# FEU31_Part3.net
KiCad netlist of a schematic drawn in Altium Designer
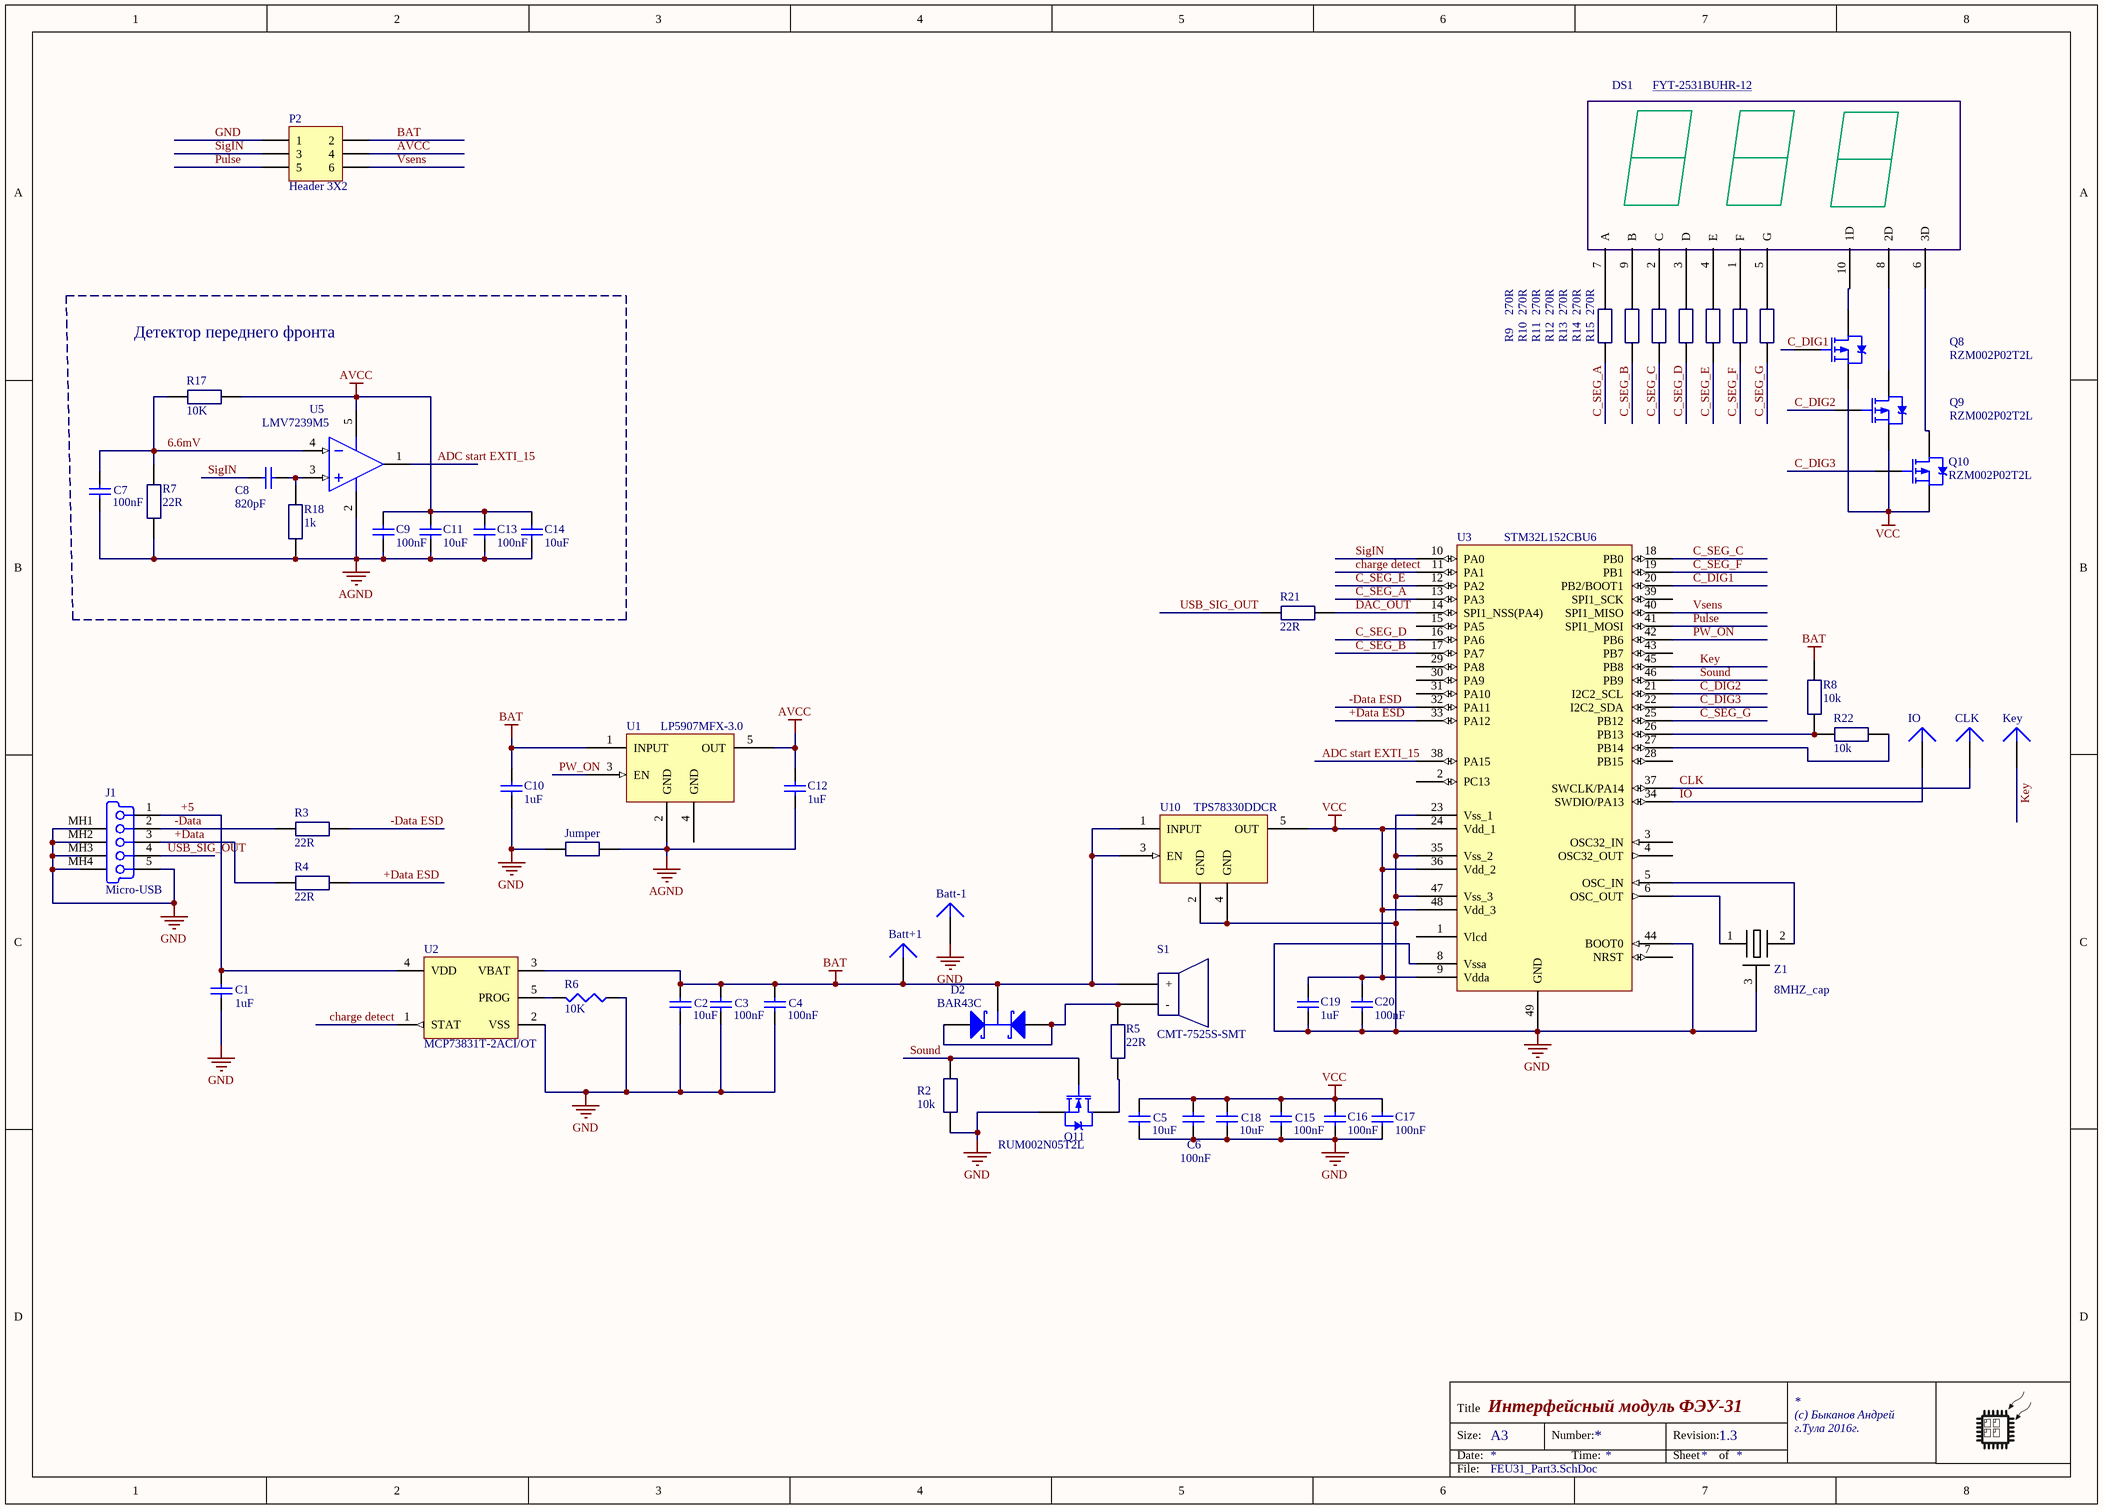
[diagram p0: FEU31_Part3.SchDoc]

(export (version "E")
  (design (tool "Eeschema 10.0.6"))
  (components
    (comp (ref "Batt+1")
      (value "~")
      (footprint "Sensor contact")
      (description "Plug")
      (fields (field (name "PUBLISHER") "Altium Limited"))
      (libsource (lib "Miscellaneous Connectors") (part "Plug"))
    )
    (comp (ref "Batt-1")
      (value "~")
      (footprint "Sensor contact")
      (description "Plug")
      (fields (field (name "PUBLISHER") "Altium Limited"))
      (libsource (lib "Miscellaneous Connectors") (part "Plug"))
    )
    (comp (ref "C1")
      (value "1uF")
      (footprint "0402 AVX")
      (description "Capacitor (Semiconductor SIM Model)")
      (fields (field (name "PUBLISHER") "Altium Limited"))
      (libsource (lib "Miscellaneous Devices") (part "Cap Semi"))
    )
    (comp (ref "C2")
      (value "10uF")
      (footprint "1608[0603]")
      (description "Capacitor (Semiconductor SIM Model)")
      (fields (field (name "PUBLISHER") "Altium Limited"))
      (libsource (lib "Miscellaneous Devices") (part "Cap Semi"))
    )
    (comp (ref "C3")
      (value "100nF")
      (footprint "0402 AVX")
      (description "Capacitor (Semiconductor SIM Model)")
      (fields (field (name "PUBLISHER") "Altium Limited"))
      (libsource (lib "Miscellaneous Devices") (part "Cap Semi"))
    )
    (comp (ref "C4")
      (value "100nF")
      (footprint "0402 AVX")
      (description "Capacitor (Semiconductor SIM Model)")
      (fields (field (name "PUBLISHER") "Altium Limited"))
      (libsource (lib "Miscellaneous Devices") (part "Cap Semi"))
    )
    (comp (ref "C5")
      (value "10uF")
      (footprint "1608[0603]")
      (description "Capacitor (Semiconductor SIM Model)")
      (fields (field (name "PUBLISHER") "Altium Limited"))
      (libsource (lib "Miscellaneous Devices") (part "Cap Semi"))
    )
    (comp (ref "C6")
      (value "100nF")
      (footprint "0402 AVX")
      (description "Capacitor (Semiconductor SIM Model)")
      (fields (field (name "PUBLISHER") "Altium Limited"))
      (libsource (lib "Miscellaneous Devices") (part "Cap Semi"))
    )
    (comp (ref "C7")
      (value "100nF")
      (footprint "0402 AVX")
      (description "Capacitor (Semiconductor SIM Model)")
      (fields (field (name "PUBLISHER") "Altium Limited"))
      (libsource (lib "Miscellaneous Devices") (part "Cap Semi"))
    )
    (comp (ref "C8")
      (value "820pF")
      (footprint "1608[0603]")
      (description "Capacitor (Semiconductor SIM Model)")
      (fields (field (name "PUBLISHER") "Altium Limited"))
      (libsource (lib "Miscellaneous Devices") (part "Cap Semi"))
    )
    (comp (ref "C9")
      (value "100nF")
      (footprint "0402 AVX")
      (description "Capacitor (Semiconductor SIM Model)")
      (fields (field (name "PUBLISHER") "Altium Limited"))
      (libsource (lib "Miscellaneous Devices") (part "Cap Semi"))
    )
    (comp (ref "C10")
      (value "1uF")
      (footprint "0402 AVX")
      (description "Capacitor (Semiconductor SIM Model)")
      (fields (field (name "PUBLISHER") "Altium Limited"))
      (libsource (lib "Miscellaneous Devices") (part "Cap Semi"))
    )
    (comp (ref "C11")
      (value "10uF")
      (footprint "1608[0603]")
      (description "Capacitor (Semiconductor SIM Model)")
      (fields (field (name "PUBLISHER") "Altium Limited"))
      (libsource (lib "Miscellaneous Devices") (part "Cap Semi"))
    )
    (comp (ref "C12")
      (value "1uF")
      (footprint "0402 AVX")
      (description "Capacitor (Semiconductor SIM Model)")
      (fields (field (name "PUBLISHER") "Altium Limited"))
      (libsource (lib "Miscellaneous Devices") (part "Cap Semi"))
    )
    (comp (ref "C13")
      (value "100nF")
      (footprint "0402 AVX")
      (description "Capacitor (Semiconductor SIM Model)")
      (fields (field (name "PUBLISHER") "Altium Limited"))
      (libsource (lib "Miscellaneous Devices") (part "Cap Semi"))
    )
    (comp (ref "C14")
      (value "10uF")
      (footprint "1608[0603]")
      (description "Capacitor (Semiconductor SIM Model)")
      (fields (field (name "PUBLISHER") "Altium Limited"))
      (libsource (lib "Miscellaneous Devices") (part "Cap Semi"))
    )
    (comp (ref "C15")
      (value "100nF")
      (footprint "0402 AVX")
      (description "Capacitor (Semiconductor SIM Model)")
      (fields (field (name "PUBLISHER") "Altium Limited"))
      (libsource (lib "Miscellaneous Devices") (part "Cap Semi"))
    )
    (comp (ref "C16")
      (value "100nF")
      (footprint "0402 AVX")
      (description "Capacitor (Semiconductor SIM Model)")
      (fields (field (name "PUBLISHER") "Altium Limited"))
      (libsource (lib "Miscellaneous Devices") (part "Cap Semi"))
    )
    (comp (ref "C17")
      (value "100nF")
      (footprint "0402 AVX")
      (description "Capacitor (Semiconductor SIM Model)")
      (fields (field (name "PUBLISHER") "Altium Limited"))
      (libsource (lib "Miscellaneous Devices") (part "Cap Semi"))
    )
    (comp (ref "C18")
      (value "10uF")
      (footprint "1608[0603]")
      (description "Capacitor (Semiconductor SIM Model)")
      (fields (field (name "PUBLISHER") "Altium Limited"))
      (libsource (lib "Miscellaneous Devices") (part "Cap Semi"))
    )
    (comp (ref "C19")
      (value "1uF")
      (footprint "0402 AVX")
      (description "Capacitor (Semiconductor SIM Model)")
      (fields (field (name "PUBLISHER") "Altium Limited"))
      (libsource (lib "Miscellaneous Devices") (part "Cap Semi"))
    )
    (comp (ref "C20")
      (value "100nF")
      (footprint "0402 AVX")
      (description "Capacitor (Semiconductor SIM Model)")
      (fields (field (name "PUBLISHER") "Altium Limited"))
      (libsource (lib "Miscellaneous Devices") (part "Cap Semi"))
    )
    (comp (ref "CLK")
      (value "~")
      (footprint "Sensor contact")
      (description "Plug")
      (fields (field (name "PUBLISHER") "Altium Limited"))
      (libsource (lib "Miscellaneous Connectors") (part "Plug"))
    )
    (comp (ref "D2")
      (value "BAR43C")
      (footprint "SOT23-3")
      (description "Schottky Barrier Double Diode")
      (fields (field (name "PUBLISHER") "Altium Limited"))
      (libsource (lib "Philips Discrete Diode - Schottky") (part "BAT54C"))
    )
    (comp (ref "DS1")
      (value "FYT-2531BUHR-12")
      (footprint "FYT-2531BUHR-12")
      (description "7-segment 3x indicator")
      (libsource (lib "My SCH library") (part "FYT-2531BUHR-12_1"))
    )
    (comp (ref "IO")
      (value "~")
      (footprint "Sensor contact")
      (description "Plug")
      (fields (field (name "PUBLISHER") "Altium Limited"))
      (libsource (lib "Miscellaneous Connectors") (part "Plug"))
    )
    (comp (ref "J1")
      (value "Micro-USB")
      (footprint "47346-0001")
      (libsource (lib "Molex Serial Bus Mini USB") (part "0481900001"))
    )
    (comp (ref "Jumper")
      (value "~")
      (footprint "0402 jumper")
      (libsource (lib "Микрон-3") (part "Resistor 0805"))
    )
    (comp (ref "Key")
      (value "~")
      (footprint "Sensor contact")
      (description "Plug")
      (fields (field (name "PUBLISHER") "Altium Limited"))
      (libsource (lib "Miscellaneous Connectors") (part "Plug"))
    )
    (comp (ref "P2")
      (value "Header 3X2")
      (footprint "PLS_FLAT_CONN_6")
      (description "Header, 3-Pin, Dual row")
      (fields (field (name "PUBLISHER") "Altium Limited"))
      (libsource (lib "Miscellaneous Connectors") (part "Header 3X2"))
    )
    (comp (ref "Q8")
      (value "RZM002P02T2L")
      (footprint "RUM002N05")
      (description "HEXFET Power MOSFET")
      (fields (field (name "PUBLISHER") "Altium Limited"))
      (libsource (lib "IR Discrete MOSFET - Power") (part "IRLML6401"))
    )
    (comp (ref "Q9")
      (value "RZM002P02T2L")
      (footprint "RUM002N05")
      (description "HEXFET Power MOSFET")
      (fields (field (name "PUBLISHER") "Altium Limited"))
      (libsource (lib "IR Discrete MOSFET - Power") (part "IRLML6401"))
    )
    (comp (ref "Q10")
      (value "RZM002P02T2L")
      (footprint "RUM002N05")
      (description "HEXFET Power MOSFET")
      (fields (field (name "PUBLISHER") "Altium Limited"))
      (libsource (lib "IR Discrete MOSFET - Power") (part "IRLML6401"))
    )
    (comp (ref "Q11")
      (value "RUM002N05T2L")
      (footprint "RUM002N05")
      (description "HEXFET Power MOSFET")
      (fields (field (name "PUBLISHER") "Altium Limited"))
      (libsource (lib "IR Discrete MOSFET - Power") (part "IRLML2402"))
    )
    (comp (ref "R2")
      (value "10k")
      (footprint "1608[0603]")
      (libsource (lib "Микрон-3") (part "Resistor 0805"))
    )
    (comp (ref "R3")
      (value "22R")
      (footprint "1608[0603]")
      (libsource (lib "Микрон-3") (part "Resistor 0805"))
    )
    (comp (ref "R4")
      (value "22R")
      (footprint "1608[0603]")
      (libsource (lib "Микрон-3") (part "Resistor 0805"))
    )
    (comp (ref "R5")
      (value "22R")
      (footprint "1608[0603]")
      (libsource (lib "Микрон-3") (part "Resistor 0805"))
    )
    (comp (ref "R6")
      (value "10K")
      (footprint "J1-0603")
      (description "Resistor")
      (fields (field (name "PUBLISHER") "Altium Limited"))
      (libsource (lib "Miscellaneous Devices") (part "Res3"))
    )
    (comp (ref "R7")
      (value "22R")
      (footprint "1608[0603]")
      (libsource (lib "Микрон-3") (part "Resistor 0805"))
    )
    (comp (ref "R8")
      (value "10k")
      (footprint "1608[0603]")
      (libsource (lib "Микрон-3") (part "Resistor 0805"))
    )
    (comp (ref "R9")
      (value "270R")
      (footprint "1608[0603]")
      (libsource (lib "Микрон-3") (part "Resistor 0805"))
    )
    (comp (ref "R10")
      (value "270R")
      (footprint "1608[0603]")
      (libsource (lib "Микрон-3") (part "Resistor 0805"))
    )
    (comp (ref "R11")
      (value "270R")
      (footprint "1608[0603]")
      (libsource (lib "Микрон-3") (part "Resistor 0805"))
    )
    (comp (ref "R12")
      (value "270R")
      (footprint "1608[0603]")
      (libsource (lib "Микрон-3") (part "Resistor 0805"))
    )
    (comp (ref "R13")
      (value "270R")
      (footprint "1608[0603]")
      (libsource (lib "Микрон-3") (part "Resistor 0805"))
    )
    (comp (ref "R14")
      (value "270R")
      (footprint "1608[0603]")
      (libsource (lib "Микрон-3") (part "Resistor 0805"))
    )
    (comp (ref "R15")
      (value "270R")
      (footprint "1608[0603]")
      (libsource (lib "Микрон-3") (part "Resistor 0805"))
    )
    (comp (ref "R17")
      (value "10K")
      (footprint "1608[0603]")
      (libsource (lib "Микрон-3") (part "Resistor 0805"))
    )
    (comp (ref "R18")
      (value "1k")
      (footprint "1608[0603]")
      (libsource (lib "Микрон-3") (part "Resistor 0805"))
    )
    (comp (ref "R21")
      (value "22R")
      (footprint "1608[0603]_RES")
      (libsource (lib "Микрон-3") (part "Resistor 0805"))
    )
    (comp (ref "R22")
      (value "10k")
      (footprint "1608[0603]")
      (libsource (lib "Микрон-3") (part "Resistor 0805"))
    )
    (comp (ref "S1")
      (value "CMT-7525S-SMT")
      (footprint "CMT-7525S-SMT")
      (libsource (lib "My SCH library") (part "CMT-7525S-SMT"))
    )
    (comp (ref "U1")
      (value "LP5907MFX-3.0")
      (footprint "TPS78330DDCR")
      (libsource (lib "My SCH library") (part "TPS78330DDCR"))
    )
    (comp (ref "U2")
      (value "MCP73831T-2ACI/OT")
      (footprint "SOT-23-OT5_N")
      (fields (field (name "PUBLISHER") "Altium Limited"))
      (libsource (lib "Microchip Power Mgt Battery Management") (part "MCP73831T-2ACI/OT"))
    )
    (comp (ref "U3")
      (value "STM32L152CBU6")
      (footprint "UFQFPN48")
      (libsource (lib "Micron-3.2") (part "STM32L152CBU6"))
    )
    (comp (ref "U5")
      (value "LMV7239M5")
      (footprint "MF05A_N")
      (fields
        (field (name "MANUFACTURER") "National Semiconductor")
        (field (name "PUBLISHER") "Altium Limited")
      )
      (libsource (lib "NSC Amplifier") (part "LMV7239M5"))
    )
    (comp (ref "U10")
      (value "TPS78330DDCR")
      (footprint "TPS78330DDCR")
      (libsource (lib "My SCH library") (part "TPS78330DDCR"))
    )
    (comp (ref "Z1")
      (value "8MHZ_cap")
      (footprint "PRQV8.00CR5010Y000")
      (libsource (lib "My SCH library") (part "8MHZ_cap"))
    )
  )
  (nets
    (net (code "1") (name "/+5") (class "Default")
      (node (ref "C1") (pin "2") (pinfunction "2_2") (pintype "passive"))
      (node (ref "J1") (pin "1") (pinfunction "V_BUS_(5V)_1") (pintype "passive"))
      (node (ref "U2") (pin "4") (pinfunction "VDD_4") (pintype "power_in"))
    )
    (net (code "2") (name "/+Data") (class "Default")
      (node (ref "J1") (pin "3") (pinfunction "D+_3") (pintype "passive"))
      (node (ref "R4") (pin "2") (pinfunction "2_2") (pintype "passive"))
    )
    (net (code "3") (name "/+Data ESD") (class "Default")
      (node (ref "R4") (pin "1") (pinfunction "A_1") (pintype "passive"))
      (node (ref "U3") (pin "33") (pinfunction "PA12_33") (pintype "bidirectional"))
    )
    (net (code "4") (name "/-Data") (class "Default")
      (node (ref "J1") (pin "2") (pinfunction "D-_2") (pintype "passive"))
      (node (ref "R3") (pin "2") (pinfunction "2_2") (pintype "passive"))
    )
    (net (code "5") (name "/-Data ESD") (class "Default")
      (node (ref "R3") (pin "1") (pinfunction "A_1") (pintype "passive"))
      (node (ref "U3") (pin "32") (pinfunction "PA11_32") (pintype "bidirectional"))
    )
    (net (code "6") (name "/6.6mV") (class "Default")
      (node (ref "C7") (pin "1") (pinfunction "1_1") (pintype "passive"))
      (node (ref "R17") (pin "1") (pinfunction "A_1") (pintype "passive"))
      (node (ref "R7") (pin "2") (pinfunction "2_2") (pintype "passive"))
      (node (ref "U5") (pin "4") (pinfunction "IN-_4") (pintype "input"))
    )
    (net (code "7") (name "/ADC start EXTI_15") (class "Default")
      (node (ref "U3") (pin "38") (pinfunction "PA15_38") (pintype "bidirectional"))
      (node (ref "U5") (pin "1") (pinfunction "VOUT_1") (pintype "open_collector"))
    )
    (net (code "8") (name "/CLK") (class "Default")
      (node (ref "CLK") (pin "1") (pinfunction "1_1") (pintype "passive"))
      (node (ref "U3") (pin "37") (pinfunction "SWCLK/PA14_37") (pintype "bidirectional"))
    )
    (net (code "9") (name "/C_DIG1") (class "Default")
      (node (ref "Q8") (pin "1") (pinfunction "G_1") (pintype "passive"))
      (node (ref "U3") (pin "20") (pinfunction "PB2/BOOT1_20") (pintype "bidirectional"))
    )
    (net (code "10") (name "/C_DIG2") (class "Default")
      (node (ref "Q9") (pin "1") (pinfunction "G_1") (pintype "passive"))
      (node (ref "U3") (pin "21") (pinfunction "I2C2_SCL_21") (pintype "bidirectional"))
    )
    (net (code "11") (name "/C_DIG3") (class "Default")
      (node (ref "Q10") (pin "1") (pinfunction "G_1") (pintype "passive"))
      (node (ref "U3") (pin "22") (pinfunction "I2C2_SDA_22") (pintype "bidirectional"))
    )
    (net (code "12") (name "/C_SEG_A") (class "Default")
      (node (ref "R12") (pin "2") (pinfunction "2_2") (pintype "passive"))
      (node (ref "U3") (pin "13") (pinfunction "PA3_13") (pintype "bidirectional"))
    )
    (net (code "13") (name "/C_SEG_B") (class "Default")
      (node (ref "R13") (pin "2") (pinfunction "2_2") (pintype "passive"))
      (node (ref "U3") (pin "17") (pinfunction "PA7_17") (pintype "bidirectional"))
    )
    (net (code "14") (name "/C_SEG_C") (class "Default")
      (node (ref "R11") (pin "2") (pinfunction "2_2") (pintype "passive"))
      (node (ref "U3") (pin "18") (pinfunction "PB0_18") (pintype "bidirectional"))
    )
    (net (code "15") (name "/C_SEG_D") (class "Default")
      (node (ref "R14") (pin "2") (pinfunction "2_2") (pintype "passive"))
      (node (ref "U3") (pin "16") (pinfunction "PA6_16") (pintype "bidirectional"))
    )
    (net (code "16") (name "/C_SEG_E") (class "Default")
      (node (ref "R10") (pin "2") (pinfunction "2_2") (pintype "passive"))
      (node (ref "U3") (pin "12") (pinfunction "PA2_12") (pintype "bidirectional"))
    )
    (net (code "17") (name "/C_SEG_F") (class "Default")
      (node (ref "R15") (pin "2") (pinfunction "2_2") (pintype "passive"))
      (node (ref "U3") (pin "19") (pinfunction "PB1_19") (pintype "bidirectional"))
    )
    (net (code "18") (name "/C_SEG_G") (class "Default")
      (node (ref "R9") (pin "2") (pinfunction "2_2") (pintype "passive"))
      (node (ref "U3") (pin "25") (pinfunction "PB12_25") (pintype "bidirectional"))
    )
    (net (code "19") (name "/DAC_OUT") (class "Default")
      (node (ref "R21") (pin "1") (pinfunction "A_1") (pintype "passive"))
      (node (ref "U3") (pin "14") (pinfunction "SPI1_NSS(PA4)_14") (pintype "bidirectional"))
    )
    (net (code "20") (name "/IO") (class "Default")
      (node (ref "IO") (pin "1") (pinfunction "1_1") (pintype "passive"))
      (node (ref "U3") (pin "34") (pinfunction "SWDIO/PA13_34") (pintype "bidirectional"))
    )
    (net (code "21") (name "/Key") (class "Default")
      (node (ref "Key") (pin "1") (pinfunction "1_1") (pintype "passive"))
      (node (ref "U3") (pin "45") (pinfunction "PB8_45") (pintype "bidirectional"))
    )
    (net (code "22") (name "/PW_ON") (class "Default")
      (node (ref "U1") (pin "3") (pinfunction "EN_3") (pintype "input"))
      (node (ref "U3") (pin "42") (pinfunction "PB6_42") (pintype "bidirectional"))
    )
    (net (code "23") (name "/Pulse") (class "Default")
      (node (ref "P2") (pin "5") (pinfunction "5_5") (pintype "passive"))
      (node (ref "U3") (pin "41") (pinfunction "SPI1_MOSI_41") (pintype "bidirectional"))
    )
    (net (code "24") (name "/SigIN") (class "Default")
      (node (ref "C8") (pin "2") (pinfunction "2_2") (pintype "passive"))
      (node (ref "P2") (pin "3") (pinfunction "3_3") (pintype "passive"))
      (node (ref "U3") (pin "10") (pinfunction "PA0_10") (pintype "bidirectional"))
    )
    (net (code "25") (name "/Sound") (class "Default")
      (node (ref "Q11") (pin "1") (pinfunction "G_1") (pintype "passive"))
      (node (ref "R2") (pin "1") (pinfunction "A_1") (pintype "passive"))
      (node (ref "U3") (pin "46") (pinfunction "PB9_46") (pintype "bidirectional"))
    )
    (net (code "26") (name "/USB_SIG_OUT") (class "Default")
      (node (ref "J1") (pin "4") (pinfunction "NC_4") (pintype "passive"))
      (node (ref "R21") (pin "2") (pinfunction "2_2") (pintype "passive"))
    )
    (net (code "27") (name "/Vsens") (class "Default")
      (node (ref "P2") (pin "6") (pinfunction "6_6") (pintype "passive"))
      (node (ref "U3") (pin "40") (pinfunction "SPI1_MISO_40") (pintype "bidirectional"))
    )
    (net (code "28") (name "/charge detect") (class "Default")
      (node (ref "U2") (pin "1") (pinfunction "STAT_1") (pintype "output"))
      (node (ref "U3") (pin "11") (pinfunction "PA1_11") (pintype "bidirectional"))
    )
    (net (code "29") (name "AGND") (class "Default")
      (node (ref "C11") (pin "2") (pinfunction "2_2") (pintype "passive"))
      (node (ref "C12") (pin "2") (pinfunction "2_2") (pintype "passive"))
      (node (ref "C13") (pin "2") (pinfunction "2_2") (pintype "passive"))
      (node (ref "C14") (pin "2") (pinfunction "2_2") (pintype "passive"))
      (node (ref "C7") (pin "2") (pinfunction "2_2") (pintype "passive"))
      (node (ref "C9") (pin "2") (pinfunction "2_2") (pintype "passive"))
      (node (ref "Jumper") (pin "1") (pinfunction "A_1") (pintype "passive"))
      (node (ref "R18") (pin "2") (pinfunction "2_2") (pintype "passive"))
      (node (ref "R7") (pin "1") (pinfunction "A_1") (pintype "passive"))
      (node (ref "U1") (pin "2") (pinfunction "GND_2") (pintype "power_in"))
      (node (ref "U5") (pin "2") (pinfunction "V-_2") (pintype "power_in"))
    )
    (net (code "30") (name "AVCC") (class "Default")
      (node (ref "C11") (pin "1") (pinfunction "1_1") (pintype "passive"))
      (node (ref "C12") (pin "1") (pinfunction "1_1") (pintype "passive"))
      (node (ref "C13") (pin "1") (pinfunction "1_1") (pintype "passive"))
      (node (ref "C14") (pin "1") (pinfunction "1_1") (pintype "passive"))
      (node (ref "C9") (pin "1") (pinfunction "1_1") (pintype "passive"))
      (node (ref "P2") (pin "4") (pinfunction "4_4") (pintype "passive"))
      (node (ref "R17") (pin "2") (pinfunction "2_2") (pintype "passive"))
      (node (ref "U1") (pin "5") (pinfunction "OUT_5") (pintype "power_in"))
      (node (ref "U5") (pin "5") (pinfunction "V+_5") (pintype "power_in"))
    )
    (net (code "31") (name "BAT") (class "Default")
      (node (ref "Batt+1") (pin "1") (pinfunction "1_1") (pintype "passive"))
      (node (ref "C10") (pin "1") (pinfunction "1_1") (pintype "passive"))
      (node (ref "C2") (pin "1") (pinfunction "1_1") (pintype "passive"))
      (node (ref "C3") (pin "1") (pinfunction "1_1") (pintype "passive"))
      (node (ref "C4") (pin "1") (pinfunction "1_1") (pintype "passive"))
      (node (ref "D2") (pin "3") (pinfunction "K_3") (pintype "passive"))
      (node (ref "P2") (pin "2") (pinfunction "2_2") (pintype "passive"))
      (node (ref "R8") (pin "1") (pinfunction "A_1") (pintype "passive"))
      (node (ref "S1") (pin "+") (pinfunction "+_+") (pintype "passive"))
      (node (ref "U1") (pin "1") (pinfunction "INPUT_1") (pintype "power_in"))
      (node (ref "U10") (pin "1") (pinfunction "INPUT_1") (pintype "power_in"))
      (node (ref "U10") (pin "3") (pinfunction "EN_3") (pintype "input"))
      (node (ref "U2") (pin "3") (pinfunction "VBAT_3") (pintype "power_in"))
    )
    (net (code "32") (name "GND") (class "Default")
      (node (ref "Batt-1") (pin "1") (pinfunction "1_1") (pintype "passive"))
      (node (ref "C1") (pin "1") (pinfunction "1_1") (pintype "passive"))
      (node (ref "C10") (pin "2") (pinfunction "2_2") (pintype "passive"))
      (node (ref "C15") (pin "2") (pinfunction "2_2") (pintype "passive"))
      (node (ref "C16") (pin "2") (pinfunction "2_2") (pintype "passive"))
      (node (ref "C17") (pin "2") (pinfunction "2_2") (pintype "passive"))
      (node (ref "C18") (pin "2") (pinfunction "2_2") (pintype "passive"))
      (node (ref "C19") (pin "2") (pinfunction "2_2") (pintype "passive"))
      (node (ref "C2") (pin "2") (pinfunction "2_2") (pintype "passive"))
      (node (ref "C20") (pin "2") (pinfunction "2_2") (pintype "passive"))
      (node (ref "C3") (pin "2") (pinfunction "2_2") (pintype "passive"))
      (node (ref "C4") (pin "2") (pinfunction "2_2") (pintype "passive"))
      (node (ref "C5") (pin "2") (pinfunction "2_2") (pintype "passive"))
      (node (ref "C6") (pin "2") (pinfunction "2_2") (pintype "passive"))
      (node (ref "J1") (pin "5") (pinfunction "GND_5") (pintype "passive"))
      (node (ref "J1") (pin "MH1") (pinfunction "Tab_MH1") (pintype "passive"))
      (node (ref "J1") (pin "MH2") (pinfunction "Tab_MH2") (pintype "passive"))
      (node (ref "J1") (pin "MH3") (pinfunction "Tab_MH3") (pintype "passive"))
      (node (ref "J1") (pin "MH4") (pinfunction "Tab_MH4") (pintype "passive"))
      (node (ref "Jumper") (pin "2") (pinfunction "2_2") (pintype "passive"))
      (node (ref "P2") (pin "1") (pinfunction "1_1") (pintype "passive"))
      (node (ref "Q11") (pin "2") (pinfunction "S_2") (pintype "passive"))
      (node (ref "R2") (pin "2") (pinfunction "2_2") (pintype "passive"))
      (node (ref "R6") (pin "1") (pinfunction "1_1") (pintype "passive"))
      (node (ref "U10") (pin "2") (pinfunction "GND_2") (pintype "power_in"))
      (node (ref "U10") (pin "4") (pinfunction "GND_4") (pintype "power_in"))
      (node (ref "U2") (pin "2") (pinfunction "VSS_2") (pintype "power_in"))
      (node (ref "U3") (pin "23") (pinfunction "Vss_1_23") (pintype "power_in"))
      (node (ref "U3") (pin "35") (pinfunction "Vss_2_35") (pintype "power_in"))
      (node (ref "U3") (pin "44") (pinfunction "BOOT0_44") (pintype "input"))
      (node (ref "U3") (pin "47") (pinfunction "Vss_3_47") (pintype "power_in"))
      (node (ref "U3") (pin "49") (pinfunction "GND_49") (pintype "power_in"))
      (node (ref "U3") (pin "8") (pinfunction "Vssa_8") (pintype "power_in"))
      (node (ref "Z1") (pin "3") (pinfunction "50_3") (pintype "passive"))
    )
    (net (code "33") (name "Net-(D2-A1)") (class "Default")
      (node (ref "D2") (pin "1") (pinfunction "A1_1") (pintype "passive"))
      (node (ref "D2") (pin "2") (pinfunction "A2_2") (pintype "passive"))
      (node (ref "R5") (pin "1") (pinfunction "A_1") (pintype "passive"))
      (node (ref "S1") (pin "-") (pinfunction "-_-") (pintype "passive"))
    )
    (net (code "34") (name "Net-(DS1-1D)") (class "Default")
      (node (ref "DS1") (pin "10") (pinfunction "1D_10") (pintype "passive"))
      (node (ref "Q8") (pin "3") (pinfunction "D_3") (pintype "passive"))
    )
    (net (code "35") (name "Net-(DS1-2D)") (class "Default")
      (node (ref "DS1") (pin "8") (pinfunction "2D_8") (pintype "passive"))
      (node (ref "Q9") (pin "3") (pinfunction "D_3") (pintype "passive"))
    )
    (net (code "36") (name "Net-(DS1-3D)") (class "Default")
      (node (ref "DS1") (pin "6") (pinfunction "3D_6") (pintype "passive"))
      (node (ref "Q10") (pin "3") (pinfunction "D_3") (pintype "passive"))
    )
    (net (code "37") (name "Net-(DS1-A)") (class "Default")
      (node (ref "DS1") (pin "7") (pinfunction "A_7") (pintype "passive"))
      (node (ref "R12") (pin "1") (pinfunction "A_1") (pintype "passive"))
    )
    (net (code "38") (name "Net-(DS1-B)") (class "Default")
      (node (ref "DS1") (pin "9") (pinfunction "B_9") (pintype "passive"))
      (node (ref "R13") (pin "1") (pinfunction "A_1") (pintype "passive"))
    )
    (net (code "39") (name "Net-(DS1-C)") (class "Default")
      (node (ref "DS1") (pin "2") (pinfunction "C_2") (pintype "passive"))
      (node (ref "R11") (pin "1") (pinfunction "A_1") (pintype "passive"))
    )
    (net (code "40") (name "Net-(DS1-D)") (class "Default")
      (node (ref "DS1") (pin "3") (pinfunction "D_3") (pintype "passive"))
      (node (ref "R14") (pin "1") (pinfunction "A_1") (pintype "passive"))
    )
    (net (code "41") (name "Net-(DS1-E)") (class "Default")
      (node (ref "DS1") (pin "4") (pinfunction "E_4") (pintype "passive"))
      (node (ref "R10") (pin "1") (pinfunction "A_1") (pintype "passive"))
    )
    (net (code "42") (name "Net-(DS1-F)") (class "Default")
      (node (ref "DS1") (pin "1") (pinfunction "F_1") (pintype "passive"))
      (node (ref "R15") (pin "1") (pinfunction "A_1") (pintype "passive"))
    )
    (net (code "43") (name "Net-(DS1-G)") (class "Default")
      (node (ref "DS1") (pin "5") (pinfunction "G_5") (pintype "passive"))
      (node (ref "R9") (pin "1") (pinfunction "A_1") (pintype "passive"))
    )
    (net (code "44") (name "Net-(Q11-D)") (class "Default")
      (node (ref "Q11") (pin "3") (pinfunction "D_3") (pintype "passive"))
      (node (ref "R5") (pin "2") (pinfunction "2_2") (pintype "passive"))
    )
    (net (code "45") (name "Net-(R18-A)") (class "Default")
      (node (ref "C8") (pin "1") (pinfunction "1_1") (pintype "passive"))
      (node (ref "R18") (pin "1") (pinfunction "A_1") (pintype "passive"))
      (node (ref "U5") (pin "3") (pinfunction "IN+_3") (pintype "input"))
    )
    (net (code "46") (name "Net-(R22-A)") (class "Default")
      (node (ref "R22") (pin "1") (pinfunction "A_1") (pintype "passive"))
      (node (ref "U3") (pin "27") (pinfunction "PB14_27") (pintype "bidirectional"))
    )
    (net (code "47") (name "Net-(U2-PROG)") (class "Default")
      (node (ref "R6") (pin "2") (pinfunction "2_2") (pintype "passive"))
      (node (ref "U2") (pin "5") (pinfunction "PROG_5") (pintype "passive"))
    )
    (net (code "48") (name "Net-(U3-OSC_IN)") (class "Default")
      (node (ref "U3") (pin "5") (pinfunction "OSC_IN_5") (pintype "input"))
      (node (ref "Z1") (pin "2") (pinfunction "2_2") (pintype "passive"))
    )
    (net (code "49") (name "Net-(U3-OSC_OUT)") (class "Default")
      (node (ref "U3") (pin "6") (pinfunction "OSC_OUT_6") (pintype "output"))
      (node (ref "Z1") (pin "1") (pinfunction "50_1") (pintype "passive"))
    )
    (net (code "50") (name "Net-(U3-PB13)") (class "Default")
      (node (ref "R22") (pin "2") (pinfunction "2_2") (pintype "passive"))
      (node (ref "R8") (pin "2") (pinfunction "2_2") (pintype "passive"))
      (node (ref "U3") (pin "26") (pinfunction "PB13_26") (pintype "bidirectional"))
    )
    (net (code "51") (name "VCC") (class "Default")
      (node (ref "C15") (pin "1") (pinfunction "1_1") (pintype "passive"))
      (node (ref "C16") (pin "1") (pinfunction "1_1") (pintype "passive"))
      (node (ref "C17") (pin "1") (pinfunction "1_1") (pintype "passive"))
      (node (ref "C18") (pin "1") (pinfunction "1_1") (pintype "passive"))
      (node (ref "C19") (pin "1") (pinfunction "1_1") (pintype "passive"))
      (node (ref "C20") (pin "1") (pinfunction "1_1") (pintype "passive"))
      (node (ref "C5") (pin "1") (pinfunction "1_1") (pintype "passive"))
      (node (ref "C6") (pin "1") (pinfunction "1_1") (pintype "passive"))
      (node (ref "Q10") (pin "2") (pinfunction "S_2") (pintype "passive"))
      (node (ref "Q8") (pin "2") (pinfunction "S_2") (pintype "passive"))
      (node (ref "Q9") (pin "2") (pinfunction "S_2") (pintype "passive"))
      (node (ref "U10") (pin "5") (pinfunction "OUT_5") (pintype "power_in"))
      (node (ref "U3") (pin "24") (pinfunction "Vdd_1_24") (pintype "power_in"))
      (node (ref "U3") (pin "36") (pinfunction "Vdd_2_36") (pintype "power_in"))
      (node (ref "U3") (pin "48") (pinfunction "Vdd_3_48") (pintype "power_in"))
      (node (ref "U3") (pin "9") (pinfunction "Vdda_9") (pintype "power_in"))
    )
    (net (code "52") (name "unconnected-(U1-GND-Pad4)") (class "Default")
      (node (ref "U1") (pin "4") (pinfunction "GND_4") (pintype "power_in"))
    )
    (net (code "53") (name "unconnected-(U3-NRST-Pad7)") (class "Default")
      (node (ref "U3") (pin "7") (pinfunction "NRST_7") (pintype "bidirectional"))
    )
    (net (code "54") (name "unconnected-(U3-OSC32_IN-Pad3)") (class "Default")
      (node (ref "U3") (pin "3") (pinfunction "OSC32_IN_3") (pintype "input"))
    )
    (net (code "55") (name "unconnected-(U3-OSC32_OUT-Pad4)") (class "Default")
      (node (ref "U3") (pin "4") (pinfunction "OSC32_OUT_4") (pintype "output"))
    )
    (net (code "56") (name "unconnected-(U3-PA5-Pad15)") (class "Default")
      (node (ref "U3") (pin "15") (pinfunction "PA5_15") (pintype "bidirectional"))
    )
    (net (code "57") (name "unconnected-(U3-PA8-Pad29)") (class "Default")
      (node (ref "U3") (pin "29") (pinfunction "PA8_29") (pintype "bidirectional"))
    )
    (net (code "58") (name "unconnected-(U3-PA9-Pad30)") (class "Default")
      (node (ref "U3") (pin "30") (pinfunction "PA9_30") (pintype "bidirectional"))
    )
    (net (code "59") (name "unconnected-(U3-PA10-Pad31)") (class "Default")
      (node (ref "U3") (pin "31") (pinfunction "PA10_31") (pintype "bidirectional"))
    )
    (net (code "60") (name "unconnected-(U3-PB7-Pad43)") (class "Default")
      (node (ref "U3") (pin "43") (pinfunction "PB7_43") (pintype "bidirectional"))
    )
    (net (code "61") (name "unconnected-(U3-PB15-Pad28)") (class "Default")
      (node (ref "U3") (pin "28") (pinfunction "PB15_28") (pintype "bidirectional"))
    )
    (net (code "62") (name "unconnected-(U3-PC13-Pad2)") (class "Default")
      (node (ref "U3") (pin "2") (pinfunction "PC13_2") (pintype "bidirectional"))
    )
    (net (code "63") (name "unconnected-(U3-SPI1_SCK-Pad39)") (class "Default")
      (node (ref "U3") (pin "39") (pinfunction "SPI1_SCK_39") (pintype "bidirectional"))
    )
    (net (code "64") (name "unconnected-(U3-Vlcd-Pad1)") (class "Default")
      (node (ref "U3") (pin "1") (pinfunction "Vlcd_1") (pintype "power_in"))
    )
  )
)
